# H-00488_-_I2C_Mux.net
KiCad netlist of a schematic drawn in Altium Designer
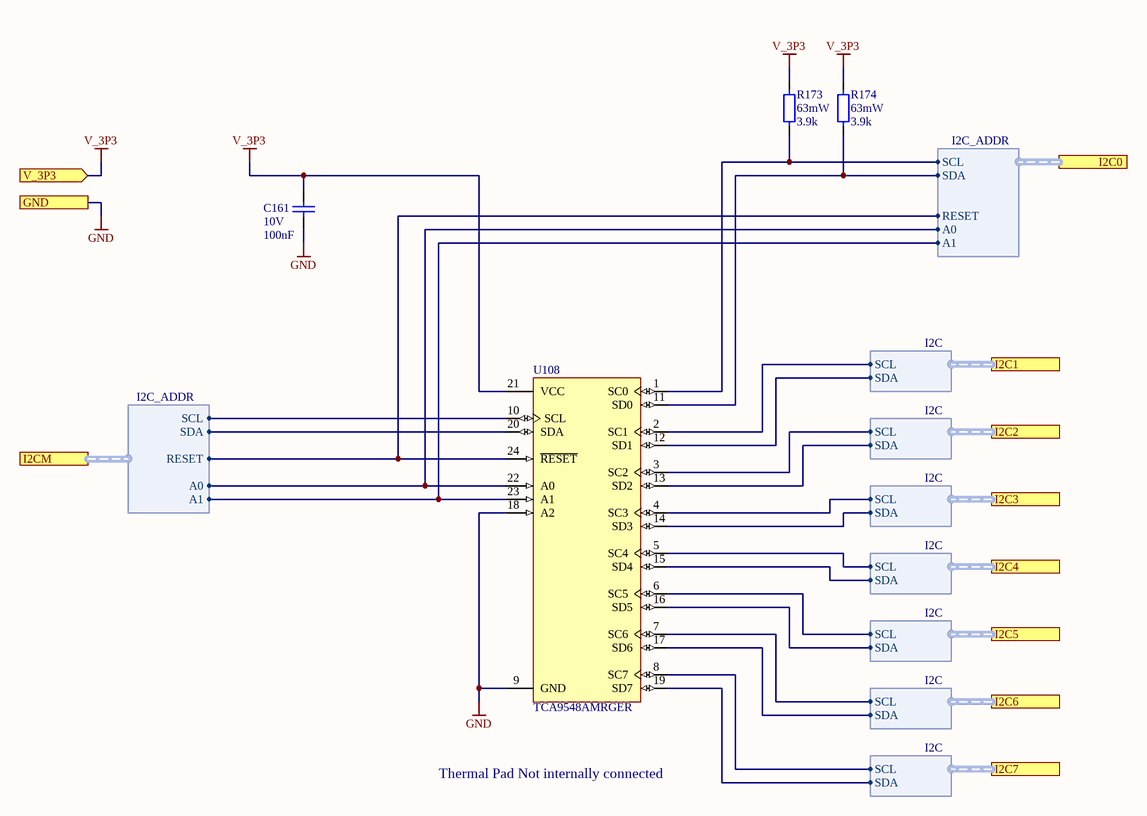
[diagram p0: H-00488 - I2C Mux.SchDoc]

(export (version "E")
  (design (tool "Eeschema 10.0.6"))
  (components
    (comp (ref "C161")
      (value "100nF")
      (footprint "CAPC100X50X55L30N")
      (description "CAP Standard 0402 (1005) 100,0nF 10V X7R (Standard)")
      (fields
        (field (name "RATED VOLTAGE") "10V")
        (field (name "TOLERANCE") "10%")
        (field (name "Comment") "C0402C104K8RACTU")
      )
      (libsource (lib "Hiber Vault") (part "CAPACITOR"))
    )
    (comp (ref "R173")
      (value "3.9k")
      (footprint "RESC100X50X40L25N")
      (description "RES Standard Thick Film 0402 3K90 ±1% 0,063W")
      (fields
        (field (name "TOLERANCE") "1%")
        (field (name "RATED POWER") "63mW")
        (field (name "Comment") "CRCW04023K90FKED")
      )
      (libsource (lib "Hiber") (part "RESISTOR-2P"))
    )
    (comp (ref "R174")
      (value "3.9k")
      (footprint "RESC100X50X40L25N")
      (description "RES Standard Thick Film 0402 3K90 ±1% 0,063W")
      (fields
        (field (name "TOLERANCE") "1%")
        (field (name "RATED POWER") "63mW")
        (field (name "Comment") "CRCW04023K90FKED")
      )
      (libsource (lib "Hiber") (part "RESISTOR-2P"))
    )
    (comp (ref "U108")
      (value "TCA9548AMRGER")
      (footprint "QFN25P50_400X400X100L40X24T270")
      (description "Multiplexer, 9548 Series, 1-Func, 1 Line Input, 8 Line Output, True Output, PQCC24")
      (libsource (lib "Hiber") (part "TCA9548AMRGER"))
    )
  )
  (nets
    (net (code "3") (name "/A0") (class "Default")
      (node (ref "U108") (pin "22") (pinfunction "A0_22") (pintype "input"))
    )
    (net (code "4") (name "/A1") (class "Default")
      (node (ref "U108") (pin "23") (pinfunction "A1_23") (pintype "input"))
    )
    (net (code "5") (name "/RESET") (class "Default")
      (node (ref "U108") (pin "24") (pinfunction "~{RESET}_24") (pintype "input"))
    )
    (net (code "8") (name "GND") (class "Default")
      (node (ref "C161") (pin "2") (pinfunction "2_2") (pintype "passive"))
      (node (ref "U108") (pin "18") (pinfunction "A2_18") (pintype "input"))
      (node (ref "U108") (pin "9") (pinfunction "GND_9") (pintype "power_in"))
    )
    (net (code "9") (name "Net-(U108-SC0)") (class "Default")
      (node (ref "R173") (pin "1") (pinfunction "1_1") (pintype "passive"))
      (node (ref "U108") (pin "1") (pinfunction "SC0_1") (pintype "bidirectional"))
    )
    (net (code "10") (name "Net-(U108-SD0)") (class "Default")
      (node (ref "R174") (pin "1") (pinfunction "1_1") (pintype "passive"))
      (node (ref "U108") (pin "11") (pinfunction "SD0_11") (pintype "bidirectional"))
    )
    (net (code "11") (name "V_3P3") (class "Default")
      (node (ref "C161") (pin "1") (pinfunction "1_1") (pintype "passive"))
      (node (ref "R173") (pin "2") (pinfunction "2_2") (pintype "passive"))
      (node (ref "R174") (pin "2") (pinfunction "2_2") (pintype "passive"))
      (node (ref "U108") (pin "21") (pinfunction "VCC_21") (pintype "power_in"))
    )
    (net (code "12") (name "unconnected-(U108-SC1-Pad2)") (class "Default")
      (node (ref "U108") (pin "2") (pinfunction "SC1_2") (pintype "bidirectional"))
    )
    (net (code "13") (name "unconnected-(U108-SC2-Pad3)") (class "Default")
      (node (ref "U108") (pin "3") (pinfunction "SC2_3") (pintype "bidirectional"))
    )
    (net (code "14") (name "unconnected-(U108-SC3-Pad4)") (class "Default")
      (node (ref "U108") (pin "4") (pinfunction "SC3_4") (pintype "bidirectional"))
    )
    (net (code "15") (name "unconnected-(U108-SC4-Pad5)") (class "Default")
      (node (ref "U108") (pin "5") (pinfunction "SC4_5") (pintype "bidirectional"))
    )
    (net (code "16") (name "unconnected-(U108-SC5-Pad6)") (class "Default")
      (node (ref "U108") (pin "6") (pinfunction "SC5_6") (pintype "bidirectional"))
    )
    (net (code "17") (name "unconnected-(U108-SC6-Pad7)") (class "Default")
      (node (ref "U108") (pin "7") (pinfunction "SC6_7") (pintype "bidirectional"))
    )
    (net (code "18") (name "unconnected-(U108-SC7-Pad8)") (class "Default")
      (node (ref "U108") (pin "8") (pinfunction "SC7_8") (pintype "bidirectional"))
    )
    (net (code "19") (name "unconnected-(U108-SCL-Pad10)") (class "Default")
      (node (ref "U108") (pin "10") (pinfunction "SCL_10") (pintype "bidirectional"))
    )
    (net (code "20") (name "unconnected-(U108-SD1-Pad12)") (class "Default")
      (node (ref "U108") (pin "12") (pinfunction "SD1_12") (pintype "bidirectional"))
    )
    (net (code "21") (name "unconnected-(U108-SD2-Pad13)") (class "Default")
      (node (ref "U108") (pin "13") (pinfunction "SD2_13") (pintype "bidirectional"))
    )
    (net (code "22") (name "unconnected-(U108-SD3-Pad14)") (class "Default")
      (node (ref "U108") (pin "14") (pinfunction "SD3_14") (pintype "bidirectional"))
    )
    (net (code "23") (name "unconnected-(U108-SD4-Pad15)") (class "Default")
      (node (ref "U108") (pin "15") (pinfunction "SD4_15") (pintype "bidirectional"))
    )
    (net (code "24") (name "unconnected-(U108-SD5-Pad16)") (class "Default")
      (node (ref "U108") (pin "16") (pinfunction "SD5_16") (pintype "bidirectional"))
    )
    (net (code "25") (name "unconnected-(U108-SD6-Pad17)") (class "Default")
      (node (ref "U108") (pin "17") (pinfunction "SD6_17") (pintype "bidirectional"))
    )
    (net (code "26") (name "unconnected-(U108-SD7-Pad19)") (class "Default")
      (node (ref "U108") (pin "19") (pinfunction "SD7_19") (pintype "bidirectional"))
    )
    (net (code "27") (name "unconnected-(U108-SDA-Pad20)") (class "Default")
      (node (ref "U108") (pin "20") (pinfunction "SDA_20") (pintype "bidirectional"))
    )
  )
)
